# opamp_module.net
KiCad netlist of a schematic drawn in EAGLE
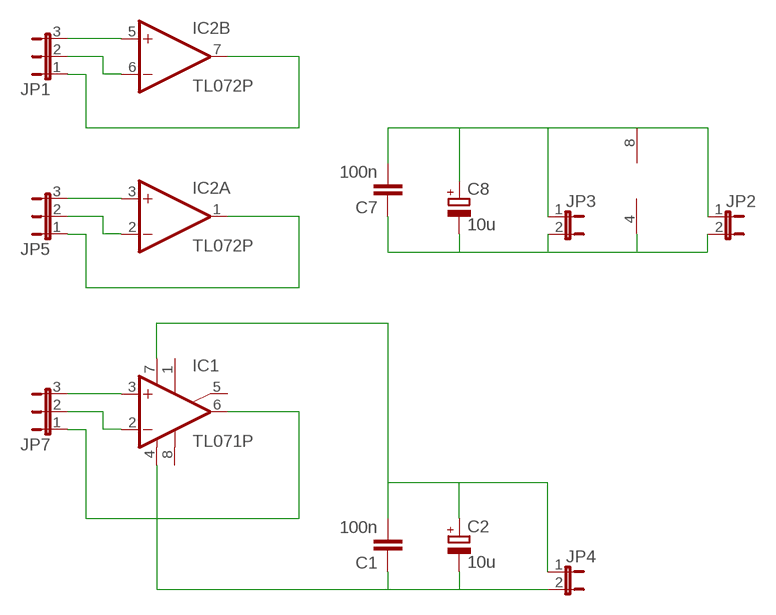
[diagram p0: schematic, sheet 1]

(export (version "E")
  (design (tool "Eeschema 10.0.6"))
  (components
    (comp (ref "C1")
      (value "100n")
      (footprint "eagle-import:C025-024X044")
      (libsource (lib "eagle-import") (part "C-EU025-024X044"))
    )
    (comp (ref "C2")
      (value "10u")
      (footprint "eagle-import:E2,5-5")
      (libsource (lib "eagle-import") (part "CPOL-EUE2.5-5"))
    )
    (comp (ref "C7")
      (value "100n")
      (footprint "eagle-import:C025-024X044")
      (libsource (lib "eagle-import") (part "C-EU025-024X044"))
    )
    (comp (ref "C8")
      (value "10u")
      (footprint "eagle-import:E2,5-5")
      (libsource (lib "eagle-import") (part "CPOL-EUE2.5-5"))
    )
    (comp (ref "IC1")
      (value "TL071P")
      (footprint "eagle-import:DIL08")
      (libsource (lib "eagle-import") (part "TL071P"))
    )
    (comp (ref "IC2")
      (value "TL072P")
      (footprint "eagle-import:DIL08")
      (libsource (lib "eagle-import") (part "TL072P"))
    )
    (comp (ref "JP1")
      (value "JP2E")
      (footprint "eagle-import:JP2")
      (libsource (lib "eagle-import") (part "JP2E"))
    )
    (comp (ref "JP2")
      (value "JP1E")
      (footprint "eagle-import:JP1")
      (libsource (lib "eagle-import") (part "JP1E"))
    )
    (comp (ref "JP3")
      (value "JP1E")
      (footprint "eagle-import:JP1")
      (libsource (lib "eagle-import") (part "JP1E"))
    )
    (comp (ref "JP4")
      (value "JP1E")
      (footprint "eagle-import:JP1")
      (libsource (lib "eagle-import") (part "JP1E"))
    )
    (comp (ref "JP5")
      (value "JP2E")
      (footprint "eagle-import:JP2")
      (libsource (lib "eagle-import") (part "JP2E"))
    )
    (comp (ref "JP7")
      (value "JP2E")
      (footprint "eagle-import:JP2")
      (libsource (lib "eagle-import") (part "JP2E"))
    )
  )
  (nets
    (net (code "1") (name "Net-(IC1-+IN)") (class "Default")
      (node (ref "IC1") (pin "3") (pinfunction "+IN_3") (pintype "input"))
      (node (ref "JP7") (pin "3") (pinfunction "3_3") (pintype "passive"))
    )
    (net (code "2") (name "Net-(IC1--IN)") (class "Default")
      (node (ref "IC1") (pin "2") (pinfunction "-IN_2") (pintype "input"))
      (node (ref "JP7") (pin "2") (pinfunction "2_2") (pintype "passive"))
    )
    (net (code "3") (name "Net-(IC1-OUT)") (class "Default")
      (node (ref "IC1") (pin "6") (pinfunction "OUT_6") (pintype "output"))
      (node (ref "JP7") (pin "1") (pinfunction "1_1") (pintype "passive"))
    )
    (net (code "4") (name "Net-(IC1-V+)") (class "Default")
      (node (ref "C1") (pin "2") (pinfunction "2_2") (pintype "passive"))
      (node (ref "C2") (pin "+") (pinfunction "+_+") (pintype "passive"))
      (node (ref "IC1") (pin "7") (pinfunction "V+_7") (pintype "power_in"))
      (node (ref "JP4") (pin "1") (pinfunction "1_1") (pintype "passive"))
    )
    (net (code "5") (name "Net-(IC1-V-)") (class "Default")
      (node (ref "C1") (pin "1") (pinfunction "1_1") (pintype "passive"))
      (node (ref "C2") (pin "-") (pinfunction "-_-") (pintype "passive"))
      (node (ref "IC1") (pin "4") (pinfunction "V-_4") (pintype "power_in"))
      (node (ref "JP4") (pin "2") (pinfunction "2_2") (pintype "passive"))
    )
    (net (code "6") (name "Net-(IC2A-+IN)") (class "Default")
      (node (ref "IC2") (pin "3") (pinfunction "+IN_3") (pintype "input"))
      (node (ref "JP5") (pin "3") (pinfunction "3_3") (pintype "passive"))
    )
    (net (code "7") (name "Net-(IC2A--IN)") (class "Default")
      (node (ref "IC2") (pin "2") (pinfunction "-IN_2") (pintype "input"))
      (node (ref "JP5") (pin "2") (pinfunction "2_2") (pintype "passive"))
    )
    (net (code "8") (name "Net-(IC2A-OUT)") (class "Default")
      (node (ref "IC2") (pin "1") (pinfunction "OUT_1") (pintype "output"))
      (node (ref "JP5") (pin "1") (pinfunction "1_1") (pintype "passive"))
    )
    (net (code "9") (name "Net-(IC2B-+IN)") (class "Default")
      (node (ref "IC2") (pin "5") (pinfunction "+IN_5") (pintype "input"))
      (node (ref "JP1") (pin "3") (pinfunction "3_3") (pintype "passive"))
    )
    (net (code "10") (name "Net-(IC2B--IN)") (class "Default")
      (node (ref "IC2") (pin "6") (pinfunction "-IN_6") (pintype "input"))
      (node (ref "JP1") (pin "2") (pinfunction "2_2") (pintype "passive"))
    )
    (net (code "11") (name "Net-(IC2B-OUT)") (class "Default")
      (node (ref "IC2") (pin "7") (pinfunction "OUT_7") (pintype "output"))
      (node (ref "JP1") (pin "1") (pinfunction "1_1") (pintype "passive"))
    )
    (net (code "12") (name "Net-(IC2C-V+)") (class "Default")
      (node (ref "C7") (pin "2") (pinfunction "2_2") (pintype "passive"))
      (node (ref "C8") (pin "+") (pinfunction "+_+") (pintype "passive"))
      (node (ref "IC2") (pin "8") (pinfunction "V+_8") (pintype "power_in"))
      (node (ref "JP2") (pin "1") (pinfunction "1_1") (pintype "passive"))
      (node (ref "JP3") (pin "1") (pinfunction "1_1") (pintype "passive"))
    )
    (net (code "13") (name "Net-(IC2C-V-)") (class "Default")
      (node (ref "C7") (pin "1") (pinfunction "1_1") (pintype "passive"))
      (node (ref "C8") (pin "-") (pinfunction "-_-") (pintype "passive"))
      (node (ref "IC2") (pin "4") (pinfunction "V-_4") (pintype "power_in"))
      (node (ref "JP2") (pin "2") (pinfunction "2_2") (pintype "passive"))
      (node (ref "JP3") (pin "2") (pinfunction "2_2") (pintype "passive"))
    )
    (net (code "14") (name "unconnected-(IC1-ON1-Pad1)") (class "Default")
      (node (ref "IC1") (pin "1") (pinfunction "ON1_1") (pintype "passive"))
    )
    (net (code "15") (name "unconnected-(IC1-ON2-Pad5)") (class "Default")
      (node (ref "IC1") (pin "5") (pinfunction "ON2_5") (pintype "passive"))
    )
    (net (code "16") (name "unconnected-(IC1-OPT-Pad8)") (class "Default")
      (node (ref "IC1") (pin "8") (pinfunction "OPT_8") (pintype "passive"))
    )
  )
)
